# Sheet2.net
KiCad netlist of a schematic drawn in Altium Designer
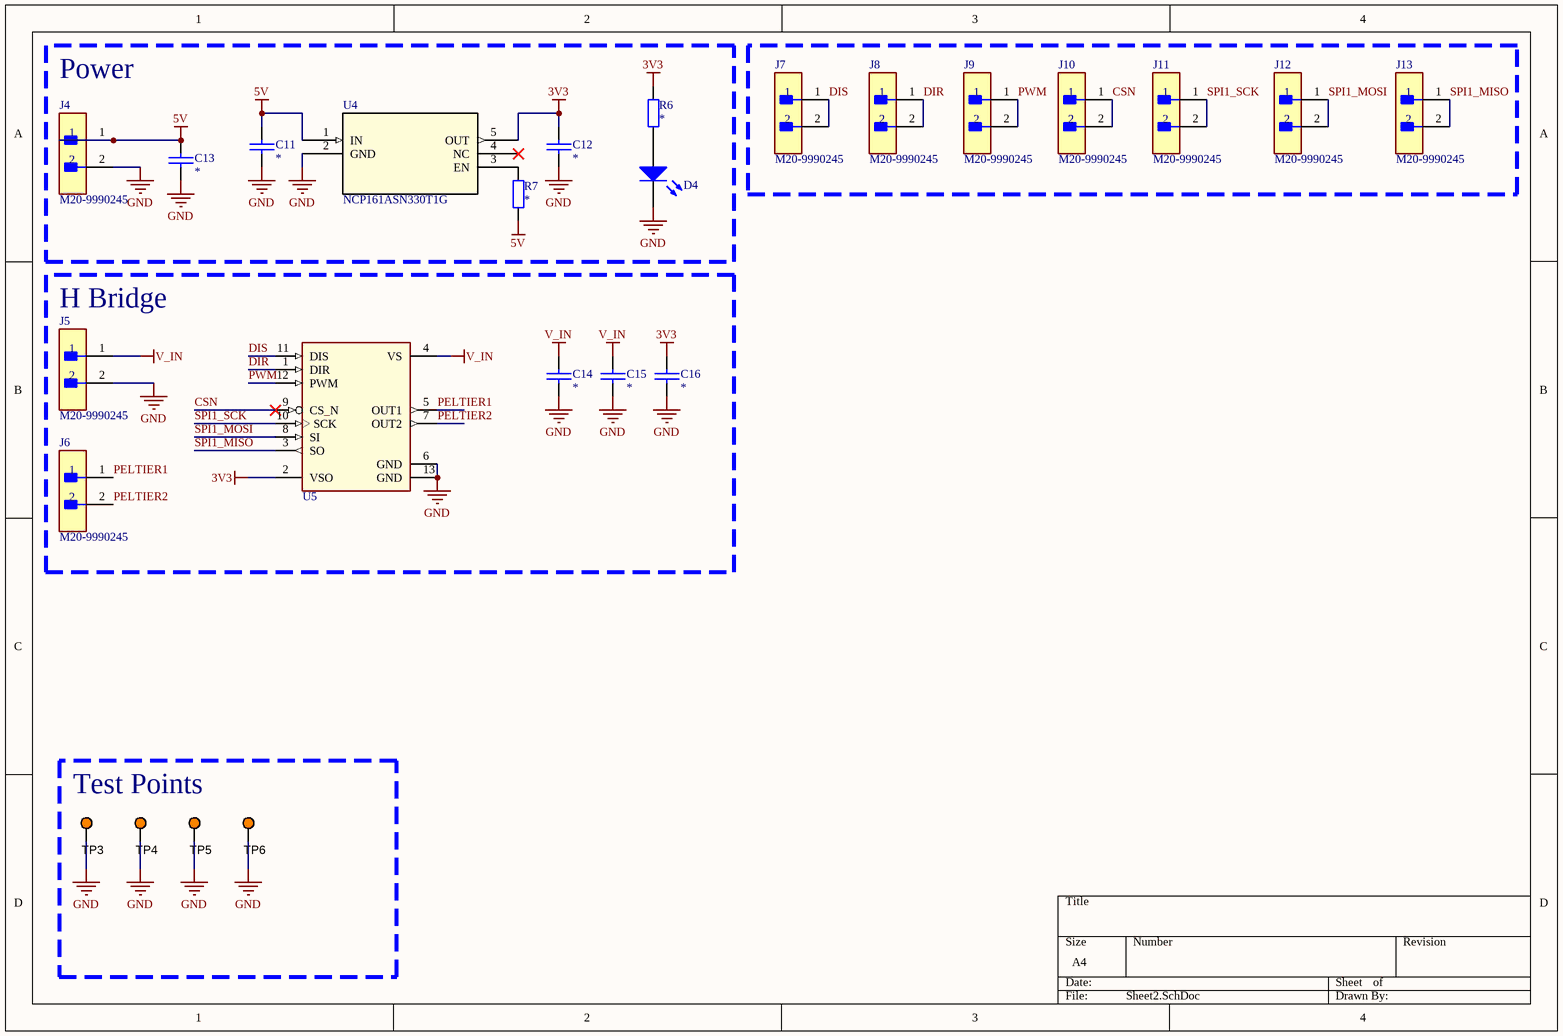
[diagram p0: Sheet2.SchDoc]

(export (version "E")
  (design (tool "Eeschema 10.0.6"))
  (components
    (comp (ref "C11")
      (value "*")
      (footprint "0805 CAP")
      (description "SMT ceramic capacitor 0805 size")
      (libsource (lib "EE209_SchLib") (part "CerCap_SMT_0805"))
    )
    (comp (ref "C12")
      (value "*")
      (footprint "0805 CAP")
      (description "SMT ceramic capacitor 0805 size")
      (libsource (lib "EE209_SchLib") (part "CerCap_SMT_0805"))
    )
    (comp (ref "C13")
      (value "*")
      (footprint "0805 CAP")
      (description "SMT ceramic capacitor 0805 size")
      (libsource (lib "EE209_SchLib") (part "CerCap_SMT_0805"))
    )
    (comp (ref "C14")
      (value "*")
      (footprint "0805 CAP")
      (description "SMT ceramic capacitor 0805 size")
      (libsource (lib "EE209_SchLib") (part "CerCap_SMT_0805"))
    )
    (comp (ref "C15")
      (value "*")
      (footprint "0805 CAP")
      (description "SMT ceramic capacitor 0805 size")
      (libsource (lib "EE209_SchLib") (part "CerCap_SMT_0805"))
    )
    (comp (ref "C16")
      (value "*")
      (footprint "0805 CAP")
      (description "SMT ceramic capacitor 0805 size")
      (libsource (lib "EE209_SchLib") (part "CerCap_SMT_0805"))
    )
    (comp (ref "D4")
      (value "LTST-C170KGKT")
      (footprint "0805 LED")
      (description "SMT LED 0805 size")
      (fields (field (name "MANUFACTURER") "Lite-On Inc."))
      (libsource (lib "EE209_SchLib") (part "LED_SMT_0805"))
    )
    (comp (ref "J4")
      (value "M20-9990245")
      (footprint "FP-M20-9990245-MFG")
      (description "CONN HEADER VERT 2POS 2.54MM")
      (fields (field (name "VOLTAGE") "50V"))
      (libsource (lib "male_headers") (part "CMP-15831-000105-1"))
    )
    (comp (ref "J5")
      (value "M20-9990245")
      (footprint "FP-M20-9990245-MFG")
      (description "CONN HEADER VERT 2POS 2.54MM")
      (fields (field (name "VOLTAGE") "50V"))
      (libsource (lib "male_headers") (part "CMP-15831-000105-1"))
    )
    (comp (ref "J6")
      (value "M20-9990245")
      (footprint "FP-M20-9990245-MFG")
      (description "CONN HEADER VERT 2POS 2.54MM")
      (fields (field (name "VOLTAGE") "50V"))
      (libsource (lib "male_headers") (part "CMP-15831-000105-1"))
    )
    (comp (ref "J7")
      (value "M20-9990245")
      (footprint "FP-M20-9990245-MFG")
      (description "CONN HEADER VERT 2POS 2.54MM")
      (fields (field (name "VOLTAGE") "50V"))
      (libsource (lib "male_headers") (part "CMP-15831-000105-1"))
    )
    (comp (ref "J8")
      (value "M20-9990245")
      (footprint "FP-M20-9990245-MFG")
      (description "CONN HEADER VERT 2POS 2.54MM")
      (fields (field (name "VOLTAGE") "50V"))
      (libsource (lib "male_headers") (part "CMP-15831-000105-1"))
    )
    (comp (ref "J9")
      (value "M20-9990245")
      (footprint "FP-M20-9990245-MFG")
      (description "CONN HEADER VERT 2POS 2.54MM")
      (fields (field (name "VOLTAGE") "50V"))
      (libsource (lib "male_headers") (part "CMP-15831-000105-1"))
    )
    (comp (ref "J10")
      (value "M20-9990245")
      (footprint "FP-M20-9990245-MFG")
      (description "CONN HEADER VERT 2POS 2.54MM")
      (fields (field (name "VOLTAGE") "50V"))
      (libsource (lib "male_headers") (part "CMP-15831-000105-1"))
    )
    (comp (ref "J11")
      (value "M20-9990245")
      (footprint "FP-M20-9990245-MFG")
      (description "CONN HEADER VERT 2POS 2.54MM")
      (fields (field (name "VOLTAGE") "50V"))
      (libsource (lib "male_headers") (part "CMP-15831-000105-1"))
    )
    (comp (ref "J12")
      (value "M20-9990245")
      (footprint "FP-M20-9990245-MFG")
      (description "CONN HEADER VERT 2POS 2.54MM")
      (fields (field (name "VOLTAGE") "50V"))
      (libsource (lib "male_headers") (part "CMP-15831-000105-1"))
    )
    (comp (ref "J13")
      (value "M20-9990245")
      (footprint "FP-M20-9990245-MFG")
      (description "CONN HEADER VERT 2POS 2.54MM")
      (fields (field (name "VOLTAGE") "50V"))
      (libsource (lib "male_headers") (part "CMP-15831-000105-1"))
    )
    (comp (ref "R6")
      (value "*")
      (footprint "0805 RES")
      (description "0805 resistor")
      (fields (field (name "PUBLISHER") "Altium Limited"))
      (libsource (lib "EE209_SchLib") (part "Res_SMT_0805"))
    )
    (comp (ref "R7")
      (value "*")
      (footprint "0805 RES")
      (description "0805 resistor")
      (fields (field (name "PUBLISHER") "Altium Limited"))
      (libsource (lib "EE209_SchLib") (part "Res_SMT_0805"))
    )
    (comp (ref "TP3")
      (value "5003")
      (footprint "EE209_PcbLib:TP_TH")
      (description "Test Point, Orange, 1-Pin THD, RoHS")
      (libsource (lib "EE209_SchLib") (part "TestPoint"))
    )
    (comp (ref "TP4")
      (value "5003")
      (footprint "EE209_PcbLib:TP_TH")
      (description "Test Point, Orange, 1-Pin THD, RoHS")
      (libsource (lib "EE209_SchLib") (part "TestPoint"))
    )
    (comp (ref "TP5")
      (value "5003")
      (footprint "EE209_PcbLib:TP_TH")
      (description "Test Point, Orange, 1-Pin THD, RoHS")
      (libsource (lib "EE209_SchLib") (part "TestPoint"))
    )
    (comp (ref "TP6")
      (value "5003")
      (footprint "EE209_PcbLib:TP_TH")
      (description "Test Point, Orange, 1-Pin THD, RoHS")
      (libsource (lib "EE209_SchLib") (part "TestPoint"))
    )
    (comp (ref "U4")
      (value "NCP161ASN330T1G")
      (footprint "SOT23_527AH_ONS")
      (description "Description")
      (fields (field (name "COPYRIGHT") "Copyright (C) 2026 Ultra Librarian. All rights reserved."))
      (libsource (lib "NCP161ASN330T1G") (part "NCP161ASN330T1G"))
    )
    (comp (ref "U5")
      (value "IFX9201SG")
      (footprint "SOP100P1030X260-13N")
      (description "6 A H-Bridge with SPI")
      (fields (field (name "MANUFACTURER") "Infineon Technologies"))
      (libsource (lib "IFX9201SG") (part "IFX9201SG"))
    )
  )
  (nets
    (net (code "1") (name "/CSN") (class "Default")
      (node (ref "J10") (pin "1") (pinfunction "1_1") (pintype "passive"))
      (node (ref "J10") (pin "2") (pinfunction "2_2") (pintype "passive"))
      (node (ref "U5") (pin "9") (pinfunction "CS_N_9") (pintype "input"))
    )
    (net (code "2") (name "/DIR") (class "Default")
      (node (ref "J8") (pin "1") (pinfunction "1_1") (pintype "passive"))
      (node (ref "J8") (pin "2") (pinfunction "2_2") (pintype "passive"))
      (node (ref "U5") (pin "1") (pinfunction "DIR_1") (pintype "input"))
    )
    (net (code "3") (name "/DIS") (class "Default")
      (node (ref "J7") (pin "1") (pinfunction "1_1") (pintype "passive"))
      (node (ref "J7") (pin "2") (pinfunction "2_2") (pintype "passive"))
      (node (ref "U5") (pin "11") (pinfunction "DIS_11") (pintype "input"))
    )
    (net (code "4") (name "/PELTIER1") (class "Default")
      (node (ref "J6") (pin "1") (pinfunction "1_1") (pintype "passive"))
      (node (ref "U5") (pin "5") (pinfunction "OUT1_5") (pintype "output"))
    )
    (net (code "5") (name "/PELTIER2") (class "Default")
      (node (ref "J6") (pin "2") (pinfunction "2_2") (pintype "passive"))
      (node (ref "U5") (pin "7") (pinfunction "OUT2_7") (pintype "output"))
    )
    (net (code "6") (name "/PWM") (class "Default")
      (node (ref "J9") (pin "1") (pinfunction "1_1") (pintype "passive"))
      (node (ref "J9") (pin "2") (pinfunction "2_2") (pintype "passive"))
      (node (ref "U5") (pin "12") (pinfunction "PWM_12") (pintype "input"))
    )
    (net (code "7") (name "/SPI1_MISO") (class "Default")
      (node (ref "J13") (pin "1") (pinfunction "1_1") (pintype "passive"))
      (node (ref "J13") (pin "2") (pinfunction "2_2") (pintype "passive"))
      (node (ref "U5") (pin "3") (pinfunction "SO_3") (pintype "output"))
    )
    (net (code "8") (name "/SPI1_MOSI") (class "Default")
      (node (ref "J12") (pin "1") (pinfunction "1_1") (pintype "passive"))
      (node (ref "J12") (pin "2") (pinfunction "2_2") (pintype "passive"))
      (node (ref "U5") (pin "8") (pinfunction "SI_8") (pintype "input"))
    )
    (net (code "9") (name "/SPI1_SCK") (class "Default")
      (node (ref "J11") (pin "1") (pinfunction "1_1") (pintype "passive"))
      (node (ref "J11") (pin "2") (pinfunction "2_2") (pintype "passive"))
      (node (ref "U5") (pin "10") (pinfunction "SCK_10") (pintype "input"))
    )
    (net (code "10") (name "3V3") (class "Default")
      (node (ref "C12") (pin "1") (pinfunction "1_1") (pintype "passive"))
      (node (ref "C16") (pin "1") (pinfunction "1_1") (pintype "passive"))
      (node (ref "R6") (pin "1") (pinfunction "1_1") (pintype "passive"))
      (node (ref "U4") (pin "5") (pinfunction "OUT_5") (pintype "output"))
      (node (ref "U5") (pin "2") (pinfunction "VSO_2") (pintype "power_in"))
    )
    (net (code "11") (name "5V") (class "Default")
      (node (ref "C11") (pin "1") (pinfunction "1_1") (pintype "passive"))
      (node (ref "C13") (pin "1") (pinfunction "1_1") (pintype "passive"))
      (node (ref "J4") (pin "1") (pinfunction "1_1") (pintype "passive"))
      (node (ref "R7") (pin "2") (pinfunction "2_2") (pintype "passive"))
      (node (ref "U4") (pin "1") (pinfunction "IN_1") (pintype "input"))
    )
    (net (code "12") (name "GND") (class "Default")
      (node (ref "C11") (pin "2") (pinfunction "2_2") (pintype "passive"))
      (node (ref "C12") (pin "2") (pinfunction "2_2") (pintype "passive"))
      (node (ref "C13") (pin "2") (pinfunction "2_2") (pintype "passive"))
      (node (ref "C14") (pin "2") (pinfunction "2_2") (pintype "passive"))
      (node (ref "C15") (pin "2") (pinfunction "2_2") (pintype "passive"))
      (node (ref "C16") (pin "2") (pinfunction "2_2") (pintype "passive"))
      (node (ref "D4") (pin "2") (pinfunction "K_2") (pintype "passive"))
      (node (ref "J4") (pin "2") (pinfunction "2_2") (pintype "passive"))
      (node (ref "J5") (pin "2") (pinfunction "2_2") (pintype "passive"))
      (node (ref "TP3") (pin "1") (pinfunction "1_1") (pintype "passive"))
      (node (ref "TP4") (pin "1") (pinfunction "1_1") (pintype "passive"))
      (node (ref "TP5") (pin "1") (pinfunction "1_1") (pintype "passive"))
      (node (ref "TP6") (pin "1") (pinfunction "1_1") (pintype "passive"))
      (node (ref "U4") (pin "2") (pinfunction "GND_2") (pintype "power_in"))
      (node (ref "U5") (pin "13") (pinfunction "GND_13") (pintype "power_in"))
      (node (ref "U5") (pin "6") (pinfunction "GND_6") (pintype "power_in"))
    )
    (net (code "13") (name "Net-(D4-A)") (class "Default")
      (node (ref "D4") (pin "1") (pinfunction "A_1") (pintype "passive"))
      (node (ref "R6") (pin "2") (pinfunction "2_2") (pintype "passive"))
    )
    (net (code "14") (name "Net-(U4-EN)") (class "Default")
      (node (ref "R7") (pin "1") (pinfunction "1_1") (pintype "passive"))
      (node (ref "U4") (pin "3") (pinfunction "EN_3") (pintype "passive"))
    )
    (net (code "15") (name "V_IN") (class "Default")
      (node (ref "C14") (pin "1") (pinfunction "1_1") (pintype "passive"))
      (node (ref "C15") (pin "1") (pinfunction "1_1") (pintype "passive"))
      (node (ref "J5") (pin "1") (pinfunction "1_1") (pintype "passive"))
      (node (ref "U5") (pin "4") (pinfunction "VS_4") (pintype "power_in"))
    )
    (net (code "16") (name "unconnected-(U4-NC-Pad4)") (class "Default")
      (node (ref "U4") (pin "4") (pinfunction "NC_4") (pintype "passive+no_connect"))
    )
  )
)
